# indicator.net
KiCad netlist of a schematic drawn in Altium Designer
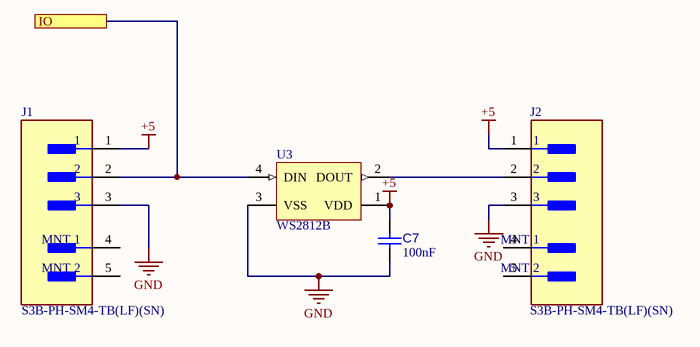
[diagram p0: indicator.SchDoc]

(export (version "E")
  (design (tool "Eeschema 10.0.6"))
  (components
    (comp (ref "C7")
      (value "100nF")
      (footprint "3")
      (description "CAP CER 100 nF 50V X7R 0603")
      (fields (field (name "TOLERANCE") "10%") (field (name "LCSC PART NUMBER") "C14663"))
      (libsource (lib "Dalhousie Formula SAE") (part "CAP-NP-2"))
    )
    (comp (ref "J1")
      (value "S3B-PH-SM4-TB(LF)(SN)")
      (footprint "FP-S3B-PH-SM4-TB_LF_SN-MFG")
      (description "CONN HEADER SMD R/A 3POS 2MM")
      (libsource (lib "Altium Content Vault") (part "38689d6f3df0f9b234c6ddcef280d85"))
    )
    (comp (ref "J2")
      (value "S3B-PH-SM4-TB(LF)(SN)")
      (footprint "FP-S3B-PH-SM4-TB_LF_SN-MFG")
      (description "CONN HEADER SMD R/A 3POS 2MM")
      (libsource (lib "") (part "38689d6f3df0f9b234c6ddcef280d85_1"))
    )
    (comp (ref "U3")
      (value "WS2812B")
      (footprint "ADAI-WS2812B_V")
      (fields (field (name "MANUFACTURER") "Adafruit Industries"))
      (libsource (lib "Dalhousie Formula SAE") (part "ADAI-WS2812B-4"))
    )
  )
  (nets
    (net (code "1") (name "+5") (class "Default")
      (node (ref "C7") (pin "2") (pinfunction "2_2") (pintype "passive"))
      (node (ref "J1") (pin "1") (pinfunction "1_1") (pintype "passive"))
      (node (ref "J2") (pin "1") (pinfunction "1_1") (pintype "passive"))
      (node (ref "U3") (pin "1") (pinfunction "VDD_1") (pintype "power_in"))
    )
    (net (code "2") (name "/IO") (class "Default")
      (node (ref "J1") (pin "2") (pinfunction "2_2") (pintype "passive"))
      (node (ref "U3") (pin "4") (pinfunction "DIN_4") (pintype "input"))
    )
    (net (code "3") (name "GND") (class "Default")
      (node (ref "C7") (pin "1") (pinfunction "1_1") (pintype "passive"))
      (node (ref "J1") (pin "3") (pinfunction "3_3") (pintype "passive"))
      (node (ref "J2") (pin "3") (pinfunction "3_3") (pintype "passive"))
      (node (ref "U3") (pin "3") (pinfunction "VSS_3") (pintype "power_in"))
    )
    (net (code "4") (name "Net-(U3-DOUT)") (class "Default")
      (node (ref "J2") (pin "2") (pinfunction "2_2") (pintype "passive"))
      (node (ref "U3") (pin "2") (pinfunction "DOUT_2") (pintype "output"))
    )
    (net (code "5") (name "unconnected-(J1-MNT_1-Pad4)") (class "Default")
      (node (ref "J1") (pin "4") (pinfunction "MNT_1_4") (pintype "passive"))
    )
    (net (code "6") (name "unconnected-(J1-MNT_2-Pad5)") (class "Default")
      (node (ref "J1") (pin "5") (pinfunction "MNT_2_5") (pintype "passive"))
    )
    (net (code "7") (name "unconnected-(J2-MNT_1-Pad4)") (class "Default")
      (node (ref "J2") (pin "4") (pinfunction "MNT_1_4") (pintype "passive"))
    )
    (net (code "8") (name "unconnected-(J2-MNT_2-Pad5)") (class "Default")
      (node (ref "J2") (pin "5") (pinfunction "MNT_2_5") (pintype "passive"))
    )
  )
)
